# Nucleo.net
KiCad netlist of a schematic drawn in Altium Designer
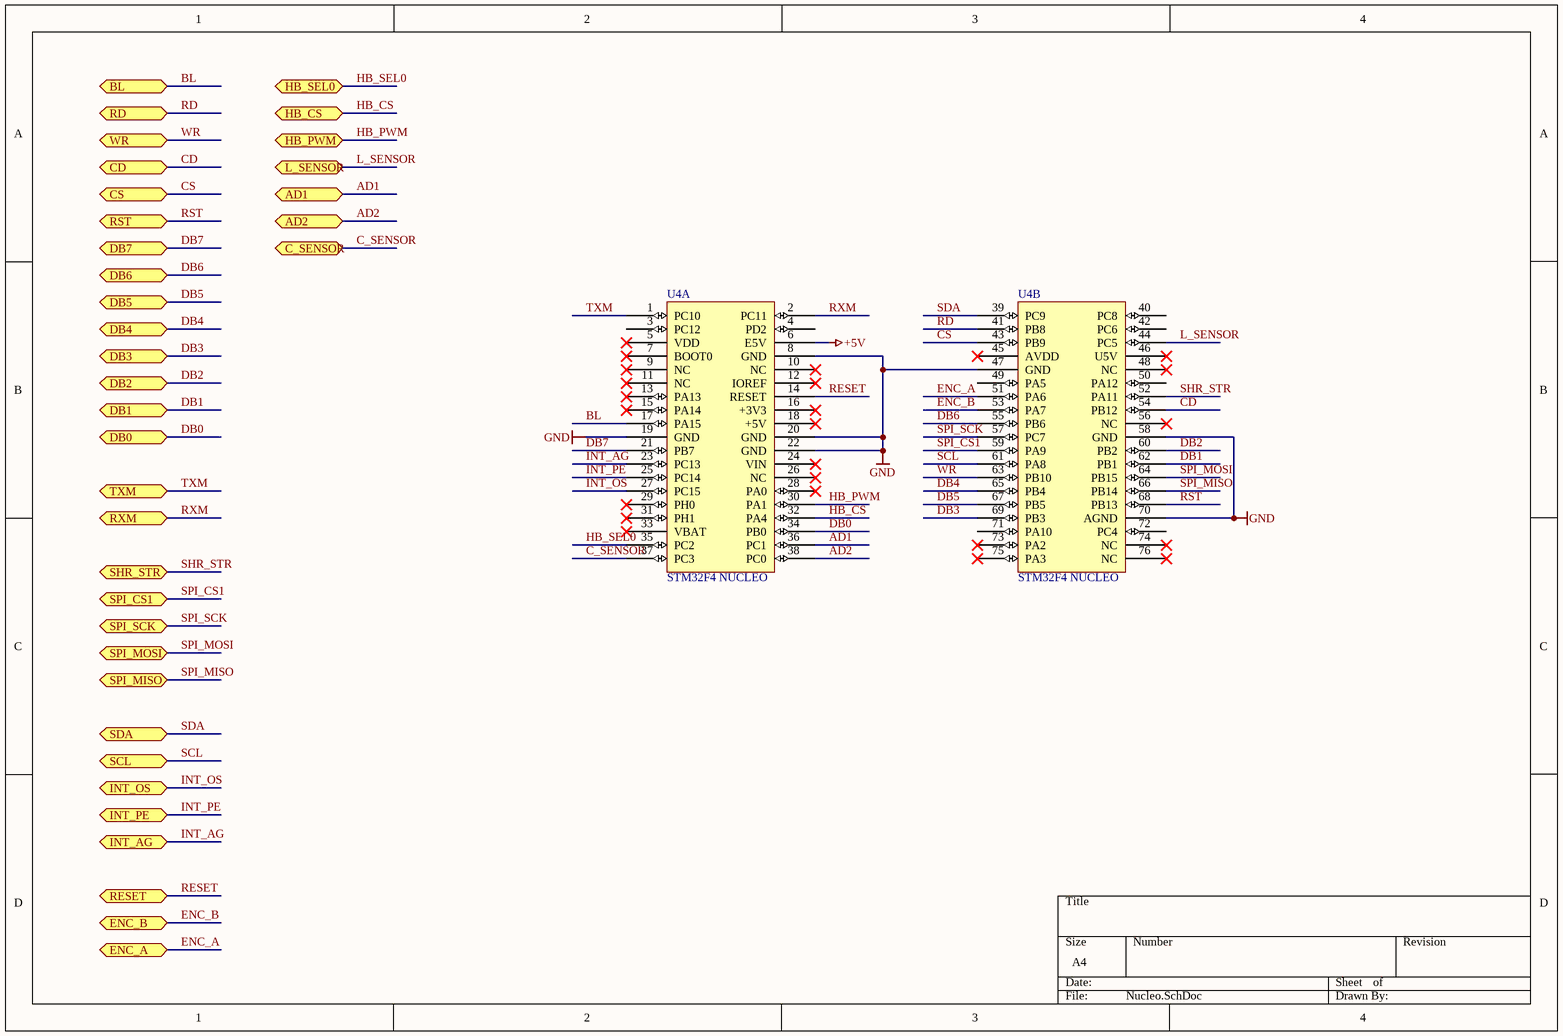
[diagram p0: Nucleo.SchDoc]

(export (version "E")
  (design (tool "Eeschema 10.0.6"))
  (components
    (comp (ref "U4")
      (value "STM32F4 NUCLEO")
      (footprint "STM32F4xx_Nucleo")
      (description "STM32F4xx Nucleo board")
      (libsource (lib "SCH_LIB") (part "NUCLEO-F446RE"))
    )
  )
  (nets
    (net (code "1") (name "+5V") (class "Default")
      (node (ref "U4") (pin "6") (pinfunction "E5V_6") (pintype "power_in"))
    )
    (net (code "2") (name "/AD1") (class "Default")
      (node (ref "U4") (pin "36") (pinfunction "PC1_36") (pintype "bidirectional"))
    )
    (net (code "3") (name "/AD2") (class "Default")
      (node (ref "U4") (pin "38") (pinfunction "PC0_38") (pintype "bidirectional"))
    )
    (net (code "4") (name "/BL") (class "Default")
      (node (ref "U4") (pin "17") (pinfunction "PA15_17") (pintype "bidirectional"))
    )
    (net (code "5") (name "/CD") (class "Default")
      (node (ref "U4") (pin "54") (pinfunction "PB12_54") (pintype "bidirectional"))
    )
    (net (code "6") (name "/CS") (class "Default")
      (node (ref "U4") (pin "43") (pinfunction "PB9_43") (pintype "bidirectional"))
    )
    (net (code "7") (name "/C_SENSOR") (class "Default")
      (node (ref "U4") (pin "37") (pinfunction "PC3_37") (pintype "bidirectional"))
    )
    (net (code "8") (name "/DB0") (class "Default")
      (node (ref "U4") (pin "34") (pinfunction "PB0_34") (pintype "bidirectional"))
    )
    (net (code "9") (name "/DB1") (class "Default")
      (node (ref "U4") (pin "62") (pinfunction "PB1_62") (pintype "bidirectional"))
    )
    (net (code "10") (name "/DB2") (class "Default")
      (node (ref "U4") (pin "60") (pinfunction "PB2_60") (pintype "bidirectional"))
    )
    (net (code "11") (name "/DB3") (class "Default")
      (node (ref "U4") (pin "69") (pinfunction "PB3_69") (pintype "bidirectional"))
    )
    (net (code "12") (name "/DB4") (class "Default")
      (node (ref "U4") (pin "65") (pinfunction "PB4_65") (pintype "bidirectional"))
    )
    (net (code "13") (name "/DB5") (class "Default")
      (node (ref "U4") (pin "67") (pinfunction "PB5_67") (pintype "bidirectional"))
    )
    (net (code "14") (name "/DB6") (class "Default")
      (node (ref "U4") (pin "55") (pinfunction "PB6_55") (pintype "bidirectional"))
    )
    (net (code "15") (name "/DB7") (class "Default")
      (node (ref "U4") (pin "21") (pinfunction "PB7_21") (pintype "bidirectional"))
    )
    (net (code "16") (name "/ENC_A") (class "Default")
      (node (ref "U4") (pin "51") (pinfunction "PA6_51") (pintype "bidirectional"))
    )
    (net (code "17") (name "/ENC_B") (class "Default")
      (node (ref "U4") (pin "53") (pinfunction "PA7_53") (pintype "bidirectional"))
    )
    (net (code "18") (name "/HB_CS") (class "Default")
      (node (ref "U4") (pin "32") (pinfunction "PA4_32") (pintype "bidirectional"))
    )
    (net (code "19") (name "/HB_PWM") (class "Default")
      (node (ref "U4") (pin "30") (pinfunction "PA1_30") (pintype "bidirectional"))
    )
    (net (code "20") (name "/HB_SEL0") (class "Default")
      (node (ref "U4") (pin "35") (pinfunction "PC2_35") (pintype "bidirectional"))
    )
    (net (code "21") (name "/INT_AG") (class "Default")
      (node (ref "U4") (pin "23") (pinfunction "PC13_23") (pintype "bidirectional"))
    )
    (net (code "22") (name "/INT_OS") (class "Default")
      (node (ref "U4") (pin "27") (pinfunction "PC15_27") (pintype "bidirectional"))
    )
    (net (code "23") (name "/INT_PE") (class "Default")
      (node (ref "U4") (pin "25") (pinfunction "PC14_25") (pintype "bidirectional"))
    )
    (net (code "24") (name "/L_SENSOR") (class "Default")
      (node (ref "U4") (pin "44") (pinfunction "PC5_44") (pintype "bidirectional"))
    )
    (net (code "25") (name "/RD") (class "Default")
      (node (ref "U4") (pin "41") (pinfunction "PB8_41") (pintype "bidirectional"))
    )
    (net (code "26") (name "/RESET") (class "Default")
      (node (ref "U4") (pin "14") (pinfunction "RESET_14") (pintype "passive"))
    )
    (net (code "27") (name "/RST") (class "Default")
      (node (ref "U4") (pin "68") (pinfunction "PB13_68") (pintype "bidirectional"))
    )
    (net (code "28") (name "/RXM") (class "Default")
      (node (ref "U4") (pin "2") (pinfunction "PC11_2") (pintype "bidirectional"))
    )
    (net (code "29") (name "/SCL") (class "Default")
      (node (ref "U4") (pin "61") (pinfunction "PA8_61") (pintype "bidirectional"))
    )
    (net (code "30") (name "/SDA") (class "Default")
      (node (ref "U4") (pin "39") (pinfunction "PC9_39") (pintype "bidirectional"))
    )
    (net (code "31") (name "/SHR_STR") (class "Default")
      (node (ref "U4") (pin "52") (pinfunction "PA11_52") (pintype "bidirectional"))
    )
    (net (code "32") (name "/SPI_CS1") (class "Default")
      (node (ref "U4") (pin "59") (pinfunction "PA9_59") (pintype "bidirectional"))
    )
    (net (code "33") (name "/SPI_MISO") (class "Default")
      (node (ref "U4") (pin "66") (pinfunction "PB14_66") (pintype "bidirectional"))
    )
    (net (code "34") (name "/SPI_MOSI") (class "Default")
      (node (ref "U4") (pin "64") (pinfunction "PB15_64") (pintype "bidirectional"))
    )
    (net (code "35") (name "/SPI_SCK") (class "Default")
      (node (ref "U4") (pin "57") (pinfunction "PC7_57") (pintype "bidirectional"))
    )
    (net (code "36") (name "/TXM") (class "Default")
      (node (ref "U4") (pin "1") (pinfunction "PC10_1") (pintype "bidirectional"))
    )
    (net (code "37") (name "/WR") (class "Default")
      (node (ref "U4") (pin "63") (pinfunction "PB10_63") (pintype "bidirectional"))
    )
    (net (code "38") (name "GND") (class "Default")
      (node (ref "U4") (pin "19") (pinfunction "GND_19") (pintype "passive"))
      (node (ref "U4") (pin "20") (pinfunction "GND_20") (pintype "passive"))
      (node (ref "U4") (pin "22") (pinfunction "GND_22") (pintype "passive"))
      (node (ref "U4") (pin "47") (pinfunction "GND_47") (pintype "passive"))
      (node (ref "U4") (pin "58") (pinfunction "GND_58") (pintype "passive"))
      (node (ref "U4") (pin "70") (pinfunction "AGND_70") (pintype "passive"))
      (node (ref "U4") (pin "8") (pinfunction "GND_8") (pintype "passive"))
    )
    (net (code "39") (name "unconnected-(U4A-+3V3-Pad16)") (class "Default")
      (node (ref "U4") (pin "16") (pinfunction "+3V3_16") (pintype "power_in+no_connect"))
    )
    (net (code "40") (name "unconnected-(U4A-+5V-Pad18)") (class "Default")
      (node (ref "U4") (pin "18") (pinfunction "+5V_18") (pintype "power_in+no_connect"))
    )
    (net (code "41") (name "unconnected-(U4A-BOOT0-Pad7)") (class "Default")
      (node (ref "U4") (pin "7") (pinfunction "BOOT0_7") (pintype "passive+no_connect"))
    )
    (net (code "42") (name "unconnected-(U4A-IOREF-Pad12)") (class "Default")
      (node (ref "U4") (pin "12") (pinfunction "IOREF_12") (pintype "passive+no_connect"))
    )
    (net (code "43") (name "unconnected-(U4A-NC-Pad9)") (class "Default")
      (node (ref "U4") (pin "9") (pinfunction "NC_9") (pintype "passive+no_connect"))
    )
    (net (code "44") (name "unconnected-(U4A-NC-Pad10)") (class "Default")
      (node (ref "U4") (pin "10") (pinfunction "NC_10") (pintype "passive+no_connect"))
    )
    (net (code "45") (name "unconnected-(U4A-NC-Pad11)") (class "Default")
      (node (ref "U4") (pin "11") (pinfunction "NC_11") (pintype "passive+no_connect"))
    )
    (net (code "46") (name "unconnected-(U4A-NC-Pad26)") (class "Default")
      (node (ref "U4") (pin "26") (pinfunction "NC_26") (pintype "passive+no_connect"))
    )
    (net (code "47") (name "unconnected-(U4A-PA0-Pad28)") (class "Default")
      (node (ref "U4") (pin "28") (pinfunction "PA0_28") (pintype "bidirectional+no_connect"))
    )
    (net (code "48") (name "unconnected-(U4A-PA13-Pad13)") (class "Default")
      (node (ref "U4") (pin "13") (pinfunction "PA13_13") (pintype "bidirectional+no_connect"))
    )
    (net (code "49") (name "unconnected-(U4A-PA14-Pad15)") (class "Default")
      (node (ref "U4") (pin "15") (pinfunction "PA14_15") (pintype "bidirectional+no_connect"))
    )
    (net (code "50") (name "unconnected-(U4A-PC12-Pad3)") (class "Default")
      (node (ref "U4") (pin "3") (pinfunction "PC12_3") (pintype "bidirectional"))
    )
    (net (code "51") (name "unconnected-(U4A-PD2-Pad4)") (class "Default")
      (node (ref "U4") (pin "4") (pinfunction "PD2_4") (pintype "bidirectional"))
    )
    (net (code "52") (name "unconnected-(U4A-PH0-Pad29)") (class "Default")
      (node (ref "U4") (pin "29") (pinfunction "PH0_29") (pintype "bidirectional+no_connect"))
    )
    (net (code "53") (name "unconnected-(U4A-PH1-Pad31)") (class "Default")
      (node (ref "U4") (pin "31") (pinfunction "PH1_31") (pintype "bidirectional+no_connect"))
    )
    (net (code "54") (name "unconnected-(U4A-VBAT-Pad33)") (class "Default")
      (node (ref "U4") (pin "33") (pinfunction "VBAT_33") (pintype "power_in+no_connect"))
    )
    (net (code "55") (name "unconnected-(U4A-VDD-Pad5)") (class "Default")
      (node (ref "U4") (pin "5") (pinfunction "VDD_5") (pintype "power_in+no_connect"))
    )
    (net (code "56") (name "unconnected-(U4A-VIN-Pad24)") (class "Default")
      (node (ref "U4") (pin "24") (pinfunction "VIN_24") (pintype "power_in+no_connect"))
    )
    (net (code "57") (name "unconnected-(U4B-AVDD-Pad45)") (class "Default")
      (node (ref "U4") (pin "45") (pinfunction "AVDD_45") (pintype "power_in+no_connect"))
    )
    (net (code "58") (name "unconnected-(U4B-NC-Pad48)") (class "Default")
      (node (ref "U4") (pin "48") (pinfunction "NC_48") (pintype "passive+no_connect"))
    )
    (net (code "59") (name "unconnected-(U4B-NC-Pad56)") (class "Default")
      (node (ref "U4") (pin "56") (pinfunction "NC_56") (pintype "passive+no_connect"))
    )
    (net (code "60") (name "unconnected-(U4B-NC-Pad74)") (class "Default")
      (node (ref "U4") (pin "74") (pinfunction "NC_74") (pintype "passive+no_connect"))
    )
    (net (code "61") (name "unconnected-(U4B-NC-Pad76)") (class "Default")
      (node (ref "U4") (pin "76") (pinfunction "NC_76") (pintype "passive+no_connect"))
    )
    (net (code "62") (name "unconnected-(U4B-PA2-Pad73)") (class "Default")
      (node (ref "U4") (pin "73") (pinfunction "PA2_73") (pintype "bidirectional+no_connect"))
    )
    (net (code "63") (name "unconnected-(U4B-PA3-Pad75)") (class "Default")
      (node (ref "U4") (pin "75") (pinfunction "PA3_75") (pintype "bidirectional+no_connect"))
    )
    (net (code "64") (name "unconnected-(U4B-PA5-Pad49)") (class "Default")
      (node (ref "U4") (pin "49") (pinfunction "PA5_49") (pintype "bidirectional"))
    )
    (net (code "65") (name "unconnected-(U4B-PA10-Pad71)") (class "Default")
      (node (ref "U4") (pin "71") (pinfunction "PA10_71") (pintype "bidirectional"))
    )
    (net (code "66") (name "unconnected-(U4B-PA12-Pad50)") (class "Default")
      (node (ref "U4") (pin "50") (pinfunction "PA12_50") (pintype "bidirectional"))
    )
    (net (code "67") (name "unconnected-(U4B-PC4-Pad72)") (class "Default")
      (node (ref "U4") (pin "72") (pinfunction "PC4_72") (pintype "bidirectional"))
    )
    (net (code "68") (name "unconnected-(U4B-PC6-Pad42)") (class "Default")
      (node (ref "U4") (pin "42") (pinfunction "PC6_42") (pintype "bidirectional"))
    )
    (net (code "69") (name "unconnected-(U4B-PC8-Pad40)") (class "Default")
      (node (ref "U4") (pin "40") (pinfunction "PC8_40") (pintype "bidirectional"))
    )
    (net (code "70") (name "unconnected-(U4B-U5V-Pad46)") (class "Default")
      (node (ref "U4") (pin "46") (pinfunction "U5V_46") (pintype "power_in+no_connect"))
    )
  )
)
